# MagcontactNRF.net
KiCad netlist of a schematic drawn in Altium Designer
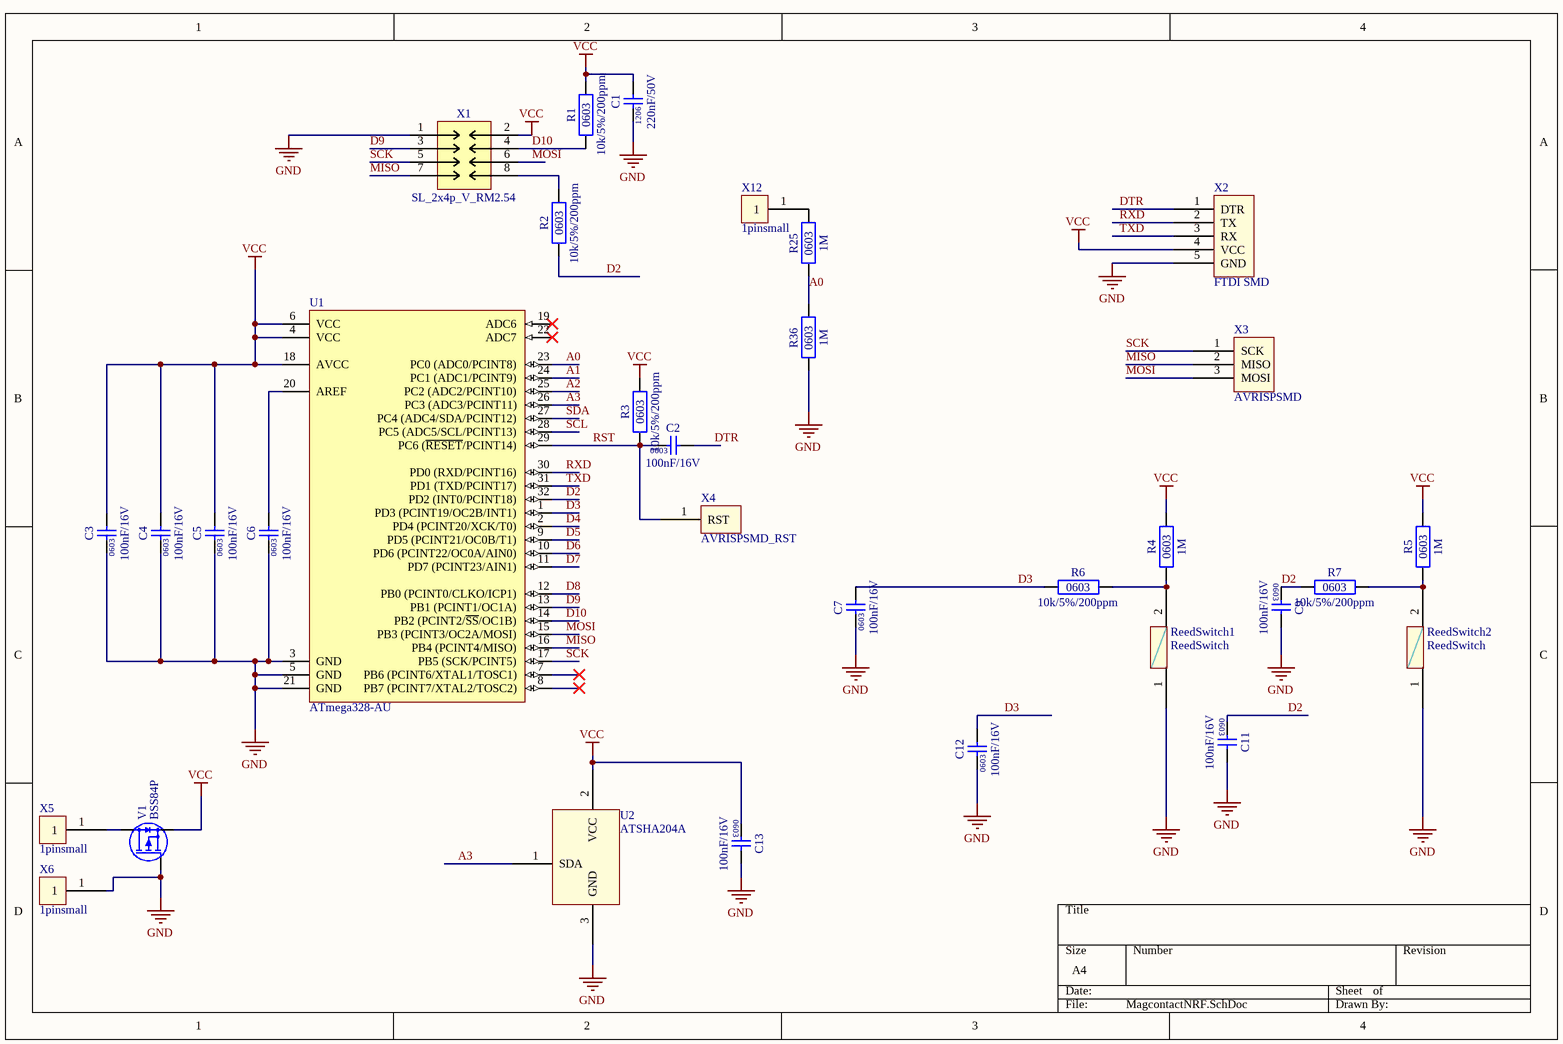
[diagram p0: MagcontactNRF.SchDoc]

(export (version "E")
  (design (tool "Eeschema 10.0.6"))
  (components
    (comp (ref "C1")
      (value "220nF/50V")
      (footprint "CAP_1206_IPC_B")
      (description "02-0087 - SMD Capacitor 1206 220nF 50V X7R")
      (fields
        (field (name "PARTNUMBER") "02-0087")
        (field (name "PUBLISHER") "RB")
        (field (name "HELPURL") "K:\\Solutions\\ETW\\Projekte\\Bibliotheken\\Bauteil-Neuanlagen\\Datenblätter\\02er-Parts\\YAGEO_Chip_Capacitors.pdf")
      )
      (libsource (lib "02_KONDENSATOREN") (part "220nF_50V_1206_02-0087"))
    )
    (comp (ref "C2")
      (value "100nF/16V")
      (footprint "CAP_0603_IPC_B")
      (description "02-0338 - SMD Capacitor 0603 100nF 16V X7R")
      (fields
        (field (name "PARTNUMBER") "02-0338")
        (field (name "HELPURL") "K:\\Solutions\\ETW\\Projekte\\Bibliotheken\\Bauteil-Neuanlagen\\Datenblätter\\02er-Parts\\")
        (field (name "PUBLISHER") "DD")
      )
      (libsource (lib "02_KONDENSATOREN") (part "100nF_16V_0603_02-0338"))
    )
    (comp (ref "C3")
      (value "100nF/16V")
      (footprint "CAP_0603_IPC_B")
      (description "02-0338 - SMD Capacitor 0603 100nF 16V X7R")
      (fields
        (field (name "PARTNUMBER") "02-0338")
        (field (name "HELPURL") "K:\\Solutions\\ETW\\Projekte\\Bibliotheken\\Bauteil-Neuanlagen\\Datenblätter\\02er-Parts\\")
        (field (name "PUBLISHER") "DD")
      )
      (libsource (lib "02_KONDENSATOREN") (part "100nF_16V_0603_02-0338"))
    )
    (comp (ref "C4")
      (value "100nF/16V")
      (footprint "CAP_0603_IPC_B")
      (description "02-0338 - SMD Capacitor 0603 100nF 16V X7R")
      (fields
        (field (name "PARTNUMBER") "02-0338")
        (field (name "HELPURL") "K:\\Solutions\\ETW\\Projekte\\Bibliotheken\\Bauteil-Neuanlagen\\Datenblätter\\02er-Parts\\")
        (field (name "PUBLISHER") "DD")
      )
      (libsource (lib "02_KONDENSATOREN") (part "100nF_16V_0603_02-0338"))
    )
    (comp (ref "C5")
      (value "100nF/16V")
      (footprint "CAP_0603_IPC_B")
      (description "02-0338 - SMD Capacitor 0603 100nF 16V X7R")
      (fields
        (field (name "PARTNUMBER") "02-0338")
        (field (name "HELPURL") "K:\\Solutions\\ETW\\Projekte\\Bibliotheken\\Bauteil-Neuanlagen\\Datenblätter\\02er-Parts\\")
        (field (name "PUBLISHER") "DD")
      )
      (libsource (lib "02_KONDENSATOREN") (part "100nF_16V_0603_02-0338"))
    )
    (comp (ref "C6")
      (value "100nF/16V")
      (footprint "CAP_0603_IPC_B")
      (description "02-0338 - SMD Capacitor 0603 100nF 16V X7R")
      (fields
        (field (name "PARTNUMBER") "02-0338")
        (field (name "HELPURL") "K:\\Solutions\\ETW\\Projekte\\Bibliotheken\\Bauteil-Neuanlagen\\Datenblätter\\02er-Parts\\")
        (field (name "PUBLISHER") "DD")
      )
      (libsource (lib "02_KONDENSATOREN") (part "100nF_16V_0603_02-0338"))
    )
    (comp (ref "C7")
      (value "100nF/16V")
      (footprint "CAP_0603_IPC_B")
      (description "02-0338 - SMD Capacitor 0603 100nF 16V X7R")
      (fields
        (field (name "PARTNUMBER") "02-0338")
        (field (name "HELPURL") "K:\\Solutions\\ETW\\Projekte\\Bibliotheken\\Bauteil-Neuanlagen\\Datenblätter\\02er-Parts\\")
        (field (name "PUBLISHER") "DD")
      )
      (libsource (lib "02_KONDENSATOREN") (part "100nF_16V_0603_02-0338"))
    )
    (comp (ref "C9")
      (value "100nF/16V")
      (footprint "CAP_0603_IPC_B")
      (description "02-0338 - SMD Capacitor 0603 100nF 16V X7R")
      (fields
        (field (name "PARTNUMBER") "02-0338")
        (field (name "HELPURL") "K:\\Solutions\\ETW\\Projekte\\Bibliotheken\\Bauteil-Neuanlagen\\Datenblätter\\02er-Parts\\")
        (field (name "PUBLISHER") "DD")
      )
      (libsource (lib "02_KONDENSATOREN") (part "100nF_16V_0603_02-0338"))
    )
    (comp (ref "C11")
      (value "100nF/16V")
      (footprint "CAP_0603_IPC_B")
      (description "02-0338 - SMD Capacitor 0603 100nF 16V X7R")
      (fields
        (field (name "PARTNUMBER") "02-0338")
        (field (name "HELPURL") "K:\\Solutions\\ETW\\Projekte\\Bibliotheken\\Bauteil-Neuanlagen\\Datenblätter\\02er-Parts\\")
        (field (name "PUBLISHER") "DD")
      )
      (libsource (lib "02_KONDENSATOREN") (part "100nF_16V_0603_02-0338"))
    )
    (comp (ref "C12")
      (value "100nF/16V")
      (footprint "CAP_0603_IPC_B")
      (description "02-0338 - SMD Capacitor 0603 100nF 16V X7R")
      (fields
        (field (name "PARTNUMBER") "02-0338")
        (field (name "HELPURL") "K:\\Solutions\\ETW\\Projekte\\Bibliotheken\\Bauteil-Neuanlagen\\Datenblätter\\02er-Parts\\")
        (field (name "PUBLISHER") "DD")
      )
      (libsource (lib "02_KONDENSATOREN") (part "100nF_16V_0603_02-0338"))
    )
    (comp (ref "C13")
      (value "100nF/16V")
      (footprint "CAP_0603_IPC_B")
      (description "02-0338 - SMD Capacitor 0603 100nF 16V X7R")
      (fields
        (field (name "PARTNUMBER") "02-0338")
        (field (name "HELPURL") "K:\\Solutions\\ETW\\Projekte\\Bibliotheken\\Bauteil-Neuanlagen\\Datenblätter\\02er-Parts\\")
        (field (name "PUBLISHER") "DD")
      )
      (libsource (lib "02_KONDENSATOREN") (part "100nF_16V_0603_02-0338"))
    )
    (comp (ref "R1")
      (value "10k/5%/200ppm")
      (footprint "RES_0603_IPC_B")
      (description "01-0424 - SMD Resistor 0603 0.063W 5%")
      (fields
        (field (name "PARTNUMBER") "01-0424")
        (field (name "HELPURL") "N:\\data\\Solutions\\etw\\Projekte\\Bibliotheken\\Bauteil-Neuanlagen\\Datenblätter\\01er-Parts\\Yageo_Chip_Resistors_0603.pdf")
        (field (name "PUBLISHER") "RB")
      )
      (libsource (lib "01_WIDERSTAENDE") (part "10k_0603_01-0424"))
    )
    (comp (ref "R2")
      (value "10k/5%/200ppm")
      (footprint "RES_0603_IPC_B")
      (description "01-0424 - SMD Resistor 0603 0.063W 5%")
      (fields
        (field (name "PARTNUMBER") "01-0424")
        (field (name "HELPURL") "N:\\data\\Solutions\\etw\\Projekte\\Bibliotheken\\Bauteil-Neuanlagen\\Datenblätter\\01er-Parts\\Yageo_Chip_Resistors_0603.pdf")
        (field (name "PUBLISHER") "RB")
      )
      (libsource (lib "01_WIDERSTAENDE") (part "10k_0603_01-0424"))
    )
    (comp (ref "R3")
      (value "10k/5%/200ppm")
      (footprint "RES_0603_IPC_B")
      (description "01-0424 - SMD Resistor 0603 0.063W 5%")
      (fields
        (field (name "PARTNUMBER") "01-0424")
        (field (name "HELPURL") "N:\\data\\Solutions\\etw\\Projekte\\Bibliotheken\\Bauteil-Neuanlagen\\Datenblätter\\01er-Parts\\Yageo_Chip_Resistors_0603.pdf")
        (field (name "PUBLISHER") "RB")
      )
      (libsource (lib "01_WIDERSTAENDE") (part "10k_0603_01-0424"))
    )
    (comp (ref "R4")
      (value "1M")
      (footprint "RES_0603_IPC_B")
      (description "01-0898 - SMD Resistor 0603  0.1W  1%")
      (fields (field (name "PARTNUMBER") "01-0898") (field (name "PUBLISHER") "DG"))
      (libsource (lib "01_WIDERSTAENDE") (part "1M_0603_01-0898"))
    )
    (comp (ref "R5")
      (value "1M")
      (footprint "RES_0603_IPC_B")
      (description "01-0898 - SMD Resistor 0603  0.1W  1%")
      (fields (field (name "PARTNUMBER") "01-0898") (field (name "PUBLISHER") "DG"))
      (libsource (lib "01_WIDERSTAENDE") (part "1M_0603_01-0898"))
    )
    (comp (ref "R6")
      (value "10k/5%/200ppm")
      (footprint "RES_0603_IPC_B")
      (description "01-0424 - SMD Resistor 0603 0.063W 5%")
      (fields
        (field (name "PARTNUMBER") "01-0424")
        (field (name "HELPURL") "N:\\data\\Solutions\\etw\\Projekte\\Bibliotheken\\Bauteil-Neuanlagen\\Datenblätter\\01er-Parts\\Yageo_Chip_Resistors_0603.pdf")
        (field (name "PUBLISHER") "RB")
      )
      (libsource (lib "01_WIDERSTAENDE") (part "10k_0603_01-0424"))
    )
    (comp (ref "R7")
      (value "10k/5%/200ppm")
      (footprint "RES_0603_IPC_B")
      (description "01-0424 - SMD Resistor 0603 0.063W 5%")
      (fields
        (field (name "PARTNUMBER") "01-0424")
        (field (name "HELPURL") "N:\\data\\Solutions\\etw\\Projekte\\Bibliotheken\\Bauteil-Neuanlagen\\Datenblätter\\01er-Parts\\Yageo_Chip_Resistors_0603.pdf")
        (field (name "PUBLISHER") "RB")
      )
      (libsource (lib "01_WIDERSTAENDE") (part "10k_0603_01-0424"))
    )
    (comp (ref "R25")
      (value "1M")
      (footprint "RES_0603_IPC_B")
      (description "01-0898 - SMD Resistor 0603  0.1W  1%")
      (fields (field (name "PARTNUMBER") "01-0898") (field (name "PUBLISHER") "DG"))
      (libsource (lib "01_WIDERSTAENDE") (part "1M_0603_01-0898"))
    )
    (comp (ref "R36")
      (value "1M")
      (footprint "RES_0603_IPC_B")
      (description "01-0898 - SMD Resistor 0603  0.1W  1%")
      (fields (field (name "PARTNUMBER") "01-0898") (field (name "PUBLISHER") "DG"))
      (libsource (lib "01_WIDERSTAENDE") (part "1M_0603_01-0898"))
    )
    (comp (ref "ReedSwitch1")
      (value "ReedSwitch")
      (footprint "MDSM-4")
      (libsource (lib "AtmegaSensor") (part "ReedSwitch"))
    )
    (comp (ref "ReedSwitch2")
      (value "ReedSwitch")
      (footprint "MDSM-4")
      (libsource (lib "AtmegaSensor") (part "ReedSwitch"))
    )
    (comp (ref "U1")
      (value "ATmega328-AU")
      (footprint "32A_N")
      (fields (field (name "PUBLISHER") "Altium Limited"))
      (libsource (lib "Atmel Microcontroller 8-Bit megaAVR") (part "ATmega328-AU"))
    )
    (comp (ref "U2") (value "ATSHA204A") (footprint "SOT23-3L") (libsource (lib "Blinds") (part "ATSHA204A")))
    (comp (ref "V1")
      (value "BSS84P")
      (footprint "SOT23-3L")
      (description "08-0275 - SIPMOS Small-Signal-Transistor")
      (fields
        (field (name "PARTNUMBER") "08-0275")
        (field (name "HELPURL") "N:\\data\\Solutions\\etw\\Projekte\\Bibliotheken\\Bauteil-Neuanlagen\\Datenblätter\\08er-Parts\\BSS84P_Rev2.6.pdf")
        (field (name "PUBLISHER") "MM")
      )
      (libsource (lib "Mainboard_abc082rn1_Rev18") (part "M_BSS84_08-0275"))
    )
    (comp (ref "X1")
      (value "SL_2x4p_V_RM2.54")
      (footprint "HEADER2X4_V_RM2.54")
      (description "NRF")
      (fields
        (field (name "PARTNUMBER") "03-0086")
        (field (name "PUBLISHER") "RB")
        (field (name "HELPURL") "N:\\data\\Solutions\\etw\\Projekte\\Bibliotheken\\Bauteil-Neuanlagen\\Datenblätter\\03er-Parts\\Pin Header Strips - Pitch 2,54 mm - Straight.pdf")
      )
      (libsource (lib "Blinds") (part "SL_2x4p_V_RM2.54_03-0086"))
    )
    (comp (ref "X2") (value "FTDI SMD") (footprint "FTDI SMD") (libsource (lib "Blinds") (part "FTDI SMD")))
    (comp (ref "X3")
      (value "AVRISPSMD")
      (footprint "AVRISPSMD")
      (libsource (lib "Blinds") (part "AVRISPSMD"))
    )
    (comp (ref "X4")
      (value "AVRISPSMD_RST")
      (footprint "AVRISPSMD - RST")
      (libsource (lib "Blinds") (part "AVRISPSMD_RST"))
    )
    (comp (ref "X5")
      (value "1pinsmall")
      (footprint "1pinsmall")
      (libsource (lib "Blinds") (part "1pinsmall"))
    )
    (comp (ref "X6")
      (value "1pinsmall")
      (footprint "1pinsmall")
      (libsource (lib "Blinds") (part "1pinsmall"))
    )
    (comp (ref "X12")
      (value "1pinsmall")
      (footprint "1pinsmall")
      (libsource (lib "Blinds") (part "1pinsmall"))
    )
  )
  (nets
    (net (code "1") (name "/A0") (class "Default")
      (node (ref "R25") (pin "1") (pintype "passive"))
      (node (ref "R36") (pin "2") (pintype "passive"))
      (node (ref "U1") (pin "23") (pinfunction "PC0_(ADC0/PCINT8)_23") (pintype "bidirectional"))
    )
    (net (code "2") (name "/A1") (class "Default")
      (node (ref "U1") (pin "24") (pinfunction "PC1_(ADC1/PCINT9)_24") (pintype "bidirectional"))
    )
    (net (code "3") (name "/A2") (class "Default")
      (node (ref "U1") (pin "25") (pinfunction "PC2_(ADC2/PCINT10)_25") (pintype "bidirectional"))
    )
    (net (code "4") (name "/A3") (class "Default")
      (node (ref "U1") (pin "26") (pinfunction "PC3_(ADC3/PCINT11)_26") (pintype "bidirectional"))
      (node (ref "U2") (pin "1") (pinfunction "SDA_1") (pintype "passive"))
    )
    (net (code "5") (name "/D2") (class "Default")
      (node (ref "C11") (pin "1") (pinfunction "1_1") (pintype "passive"))
      (node (ref "C9") (pin "1") (pinfunction "1_1") (pintype "passive"))
      (node (ref "R2") (pin "1") (pintype "passive"))
      (node (ref "R7") (pin "1") (pintype "passive"))
      (node (ref "U1") (pin "32") (pinfunction "PD2_(INT0/PCINT18)_32") (pintype "bidirectional"))
    )
    (net (code "6") (name "/D3") (class "Default")
      (node (ref "C12") (pin "2") (pinfunction "2_2") (pintype "passive"))
      (node (ref "C7") (pin "2") (pinfunction "2_2") (pintype "passive"))
      (node (ref "R6") (pin "1") (pintype "passive"))
      (node (ref "U1") (pin "1") (pinfunction "PD3_(PCINT19/OC2B/INT1)_1") (pintype "bidirectional"))
    )
    (net (code "7") (name "/D4") (class "Default")
      (node (ref "U1") (pin "2") (pinfunction "PD4_(PCINT20/XCK/T0)_2") (pintype "bidirectional"))
    )
    (net (code "8") (name "/D5") (class "Default")
      (node (ref "U1") (pin "9") (pinfunction "PD5_(PCINT21/OC0B/T1)_9") (pintype "bidirectional"))
    )
    (net (code "9") (name "/D6") (class "Default")
      (node (ref "U1") (pin "10") (pinfunction "PD6_(PCINT22/OC0A/AIN0)_10") (pintype "bidirectional"))
    )
    (net (code "10") (name "/D7") (class "Default")
      (node (ref "U1") (pin "11") (pinfunction "PD7_(PCINT23/AIN1)_11") (pintype "bidirectional"))
    )
    (net (code "11") (name "/D8") (class "Default")
      (node (ref "U1") (pin "12") (pinfunction "PB0_(PCINT0/CLKO/ICP1)_12") (pintype "bidirectional"))
    )
    (net (code "12") (name "/D9") (class "Default")
      (node (ref "U1") (pin "13") (pinfunction "PB1_(PCINT1/OC1A)_13") (pintype "bidirectional"))
      (node (ref "X1") (pin "3") (pinfunction "3_3") (pintype "passive"))
    )
    (net (code "13") (name "/D10") (class "Default")
      (node (ref "R1") (pin "1") (pintype "passive"))
      (node (ref "U1") (pin "14") (pinfunction "PB2_(PCINT2/~{SS}/OC1B)_14") (pintype "bidirectional"))
      (node (ref "X1") (pin "4") (pinfunction "4_4") (pintype "passive"))
    )
    (net (code "14") (name "/DTR") (class "Default")
      (node (ref "C2") (pin "2") (pinfunction "2_2") (pintype "passive"))
      (node (ref "X2") (pin "1") (pinfunction "DTR_1") (pintype "passive"))
    )
    (net (code "15") (name "/MISO") (class "Default")
      (node (ref "U1") (pin "16") (pinfunction "PB4_(PCINT4/MISO)_16") (pintype "bidirectional"))
      (node (ref "X1") (pin "7") (pinfunction "7_7") (pintype "passive"))
      (node (ref "X3") (pin "2") (pinfunction "MISO_2") (pintype "passive"))
    )
    (net (code "16") (name "/MOSI") (class "Default")
      (node (ref "U1") (pin "15") (pinfunction "PB3_(PCINT3/OC2A/MOSI)_15") (pintype "bidirectional"))
      (node (ref "X1") (pin "6") (pinfunction "6_6") (pintype "passive"))
      (node (ref "X3") (pin "3") (pinfunction "MOSI_3") (pintype "passive"))
    )
    (net (code "17") (name "/RST") (class "Default")
      (node (ref "C2") (pin "1") (pinfunction "1_1") (pintype "passive"))
      (node (ref "R3") (pin "1") (pintype "passive"))
      (node (ref "U1") (pin "29") (pinfunction "PC6_(~{RESET}/PCINT14)_29") (pintype "bidirectional"))
      (node (ref "X4") (pin "1") (pinfunction "RST_1") (pintype "passive"))
    )
    (net (code "18") (name "/RXD") (class "Default")
      (node (ref "U1") (pin "30") (pinfunction "PD0_(RXD/PCINT16)_30") (pintype "bidirectional"))
      (node (ref "X2") (pin "2") (pinfunction "TX_2") (pintype "passive"))
    )
    (net (code "19") (name "/SCK") (class "Default")
      (node (ref "U1") (pin "17") (pinfunction "PB5_(SCK/PCINT5)_17") (pintype "bidirectional"))
      (node (ref "X1") (pin "5") (pinfunction "5_5") (pintype "passive"))
      (node (ref "X3") (pin "1") (pinfunction "SCK_1") (pintype "passive"))
    )
    (net (code "20") (name "/SCL") (class "Default")
      (node (ref "U1") (pin "28") (pinfunction "PC5_(ADC5/SCL/PCINT13)_28") (pintype "bidirectional"))
    )
    (net (code "21") (name "/SDA") (class "Default")
      (node (ref "U1") (pin "27") (pinfunction "PC4_(ADC4/SDA/PCINT12)_27") (pintype "bidirectional"))
    )
    (net (code "22") (name "/TXD") (class "Default")
      (node (ref "U1") (pin "31") (pinfunction "PD1_(TXD/PCINT17)_31") (pintype "bidirectional"))
      (node (ref "X2") (pin "3") (pinfunction "RX_3") (pintype "passive"))
    )
    (net (code "23") (name "GND") (class "Default")
      (node (ref "C1") (pin "1") (pinfunction "1_1") (pintype "passive"))
      (node (ref "C11") (pin "2") (pinfunction "2_2") (pintype "passive"))
      (node (ref "C12") (pin "1") (pinfunction "1_1") (pintype "passive"))
      (node (ref "C13") (pin "2") (pinfunction "2_2") (pintype "passive"))
      (node (ref "C3") (pin "1") (pinfunction "1_1") (pintype "passive"))
      (node (ref "C4") (pin "1") (pinfunction "1_1") (pintype "passive"))
      (node (ref "C5") (pin "1") (pinfunction "1_1") (pintype "passive"))
      (node (ref "C6") (pin "1") (pinfunction "1_1") (pintype "passive"))
      (node (ref "C7") (pin "1") (pinfunction "1_1") (pintype "passive"))
      (node (ref "C9") (pin "2") (pinfunction "2_2") (pintype "passive"))
      (node (ref "R36") (pin "1") (pintype "passive"))
      (node (ref "ReedSwitch1") (pin "1") (pintype "passive"))
      (node (ref "ReedSwitch2") (pin "1") (pintype "passive"))
      (node (ref "U1") (pin "21") (pinfunction "GND_21") (pintype "power_in"))
      (node (ref "U1") (pin "3") (pinfunction "GND_3") (pintype "power_in"))
      (node (ref "U1") (pin "5") (pinfunction "GND_5") (pintype "power_in"))
      (node (ref "U2") (pin "3") (pinfunction "GND_3") (pintype "passive"))
      (node (ref "V1") (pin "G") (pinfunction "G_G") (pintype "passive"))
      (node (ref "X1") (pin "1") (pinfunction "1_1") (pintype "passive"))
      (node (ref "X2") (pin "5") (pinfunction "GND_5") (pintype "passive"))
      (node (ref "X6") (pin "1") (pinfunction "1_1") (pintype "passive"))
    )
    (net (code "24") (name "Net-(R2-Pad2)") (class "Default")
      (node (ref "R2") (pin "2") (pintype "passive"))
      (node (ref "X1") (pin "8") (pinfunction "8_8") (pintype "passive"))
    )
    (net (code "25") (name "Net-(R4-Pad1)") (class "Default")
      (node (ref "R4") (pin "1") (pintype "passive"))
      (node (ref "R6") (pin "2") (pintype "passive"))
      (node (ref "ReedSwitch1") (pin "2") (pintype "passive"))
    )
    (net (code "26") (name "Net-(R5-Pad1)") (class "Default")
      (node (ref "R5") (pin "1") (pintype "passive"))
      (node (ref "R7") (pin "2") (pintype "passive"))
      (node (ref "ReedSwitch2") (pin "2") (pintype "passive"))
    )
    (net (code "27") (name "Net-(R25-Pad2)") (class "Default")
      (node (ref "R25") (pin "2") (pintype "passive"))
      (node (ref "X12") (pin "1") (pinfunction "1_1") (pintype "passive"))
    )
    (net (code "28") (name "Net-(U1-AREF)") (class "Default")
      (node (ref "C6") (pin "2") (pinfunction "2_2") (pintype "passive"))
      (node (ref "U1") (pin "20") (pinfunction "AREF_20") (pintype "passive"))
    )
    (net (code "29") (name "Net-(V1-PadD)") (class "Default")
      (node (ref "V1") (pin "D") (pinfunction "D_D") (pintype "passive"))
      (node (ref "X5") (pin "1") (pinfunction "1_1") (pintype "passive"))
    )
    (net (code "30") (name "VCC") (class "Default")
      (node (ref "C1") (pin "2") (pinfunction "2_2") (pintype "passive"))
      (node (ref "C13") (pin "1") (pinfunction "1_1") (pintype "passive"))
      (node (ref "C3") (pin "2") (pinfunction "2_2") (pintype "passive"))
      (node (ref "C4") (pin "2") (pinfunction "2_2") (pintype "passive"))
      (node (ref "C5") (pin "2") (pinfunction "2_2") (pintype "passive"))
      (node (ref "R1") (pin "2") (pintype "passive"))
      (node (ref "R3") (pin "2") (pintype "passive"))
      (node (ref "R4") (pin "2") (pintype "passive"))
      (node (ref "R5") (pin "2") (pintype "passive"))
      (node (ref "U1") (pin "18") (pinfunction "AVCC_18") (pintype "power_in"))
      (node (ref "U1") (pin "4") (pinfunction "VCC_4") (pintype "power_in"))
      (node (ref "U1") (pin "6") (pinfunction "VCC_6") (pintype "power_in"))
      (node (ref "U2") (pin "2") (pinfunction "VCC_2") (pintype "passive"))
      (node (ref "V1") (pin "S") (pinfunction "S_S") (pintype "passive"))
      (node (ref "X1") (pin "2") (pinfunction "2_2") (pintype "passive"))
      (node (ref "X2") (pin "4") (pinfunction "VCC_4") (pintype "passive"))
    )
    (net (code "31") (name "unconnected-(U1-ADC6-Pad19)") (class "Default")
      (node (ref "U1") (pin "19") (pinfunction "ADC6_19") (pintype "input+no_connect"))
    )
    (net (code "32") (name "unconnected-(U1-ADC7-Pad22)") (class "Default")
      (node (ref "U1") (pin "22") (pinfunction "ADC7_22") (pintype "input+no_connect"))
    )
    (net (code "33") (name "unconnected-(U1-PB6_(PCINT6{slash}XTAL1{slash}TOSC1)-Pad7)") (class "Default")
      (node (ref "U1") (pin "7") (pinfunction "PB6_(PCINT6/XTAL1/TOSC1)_7") (pintype "bidirectional+no_connect"))
    )
    (net (code "34") (name "unconnected-(U1-PB7_(PCINT7{slash}XTAL2{slash}TOSC2)-Pad8)") (class "Default")
      (node (ref "U1") (pin "8") (pinfunction "PB7_(PCINT7/XTAL2/TOSC2)_8") (pintype "bidirectional+no_connect"))
    )
  )
)
